# schem.net
KiCad netlist of a schematic drawn in EasyEDA
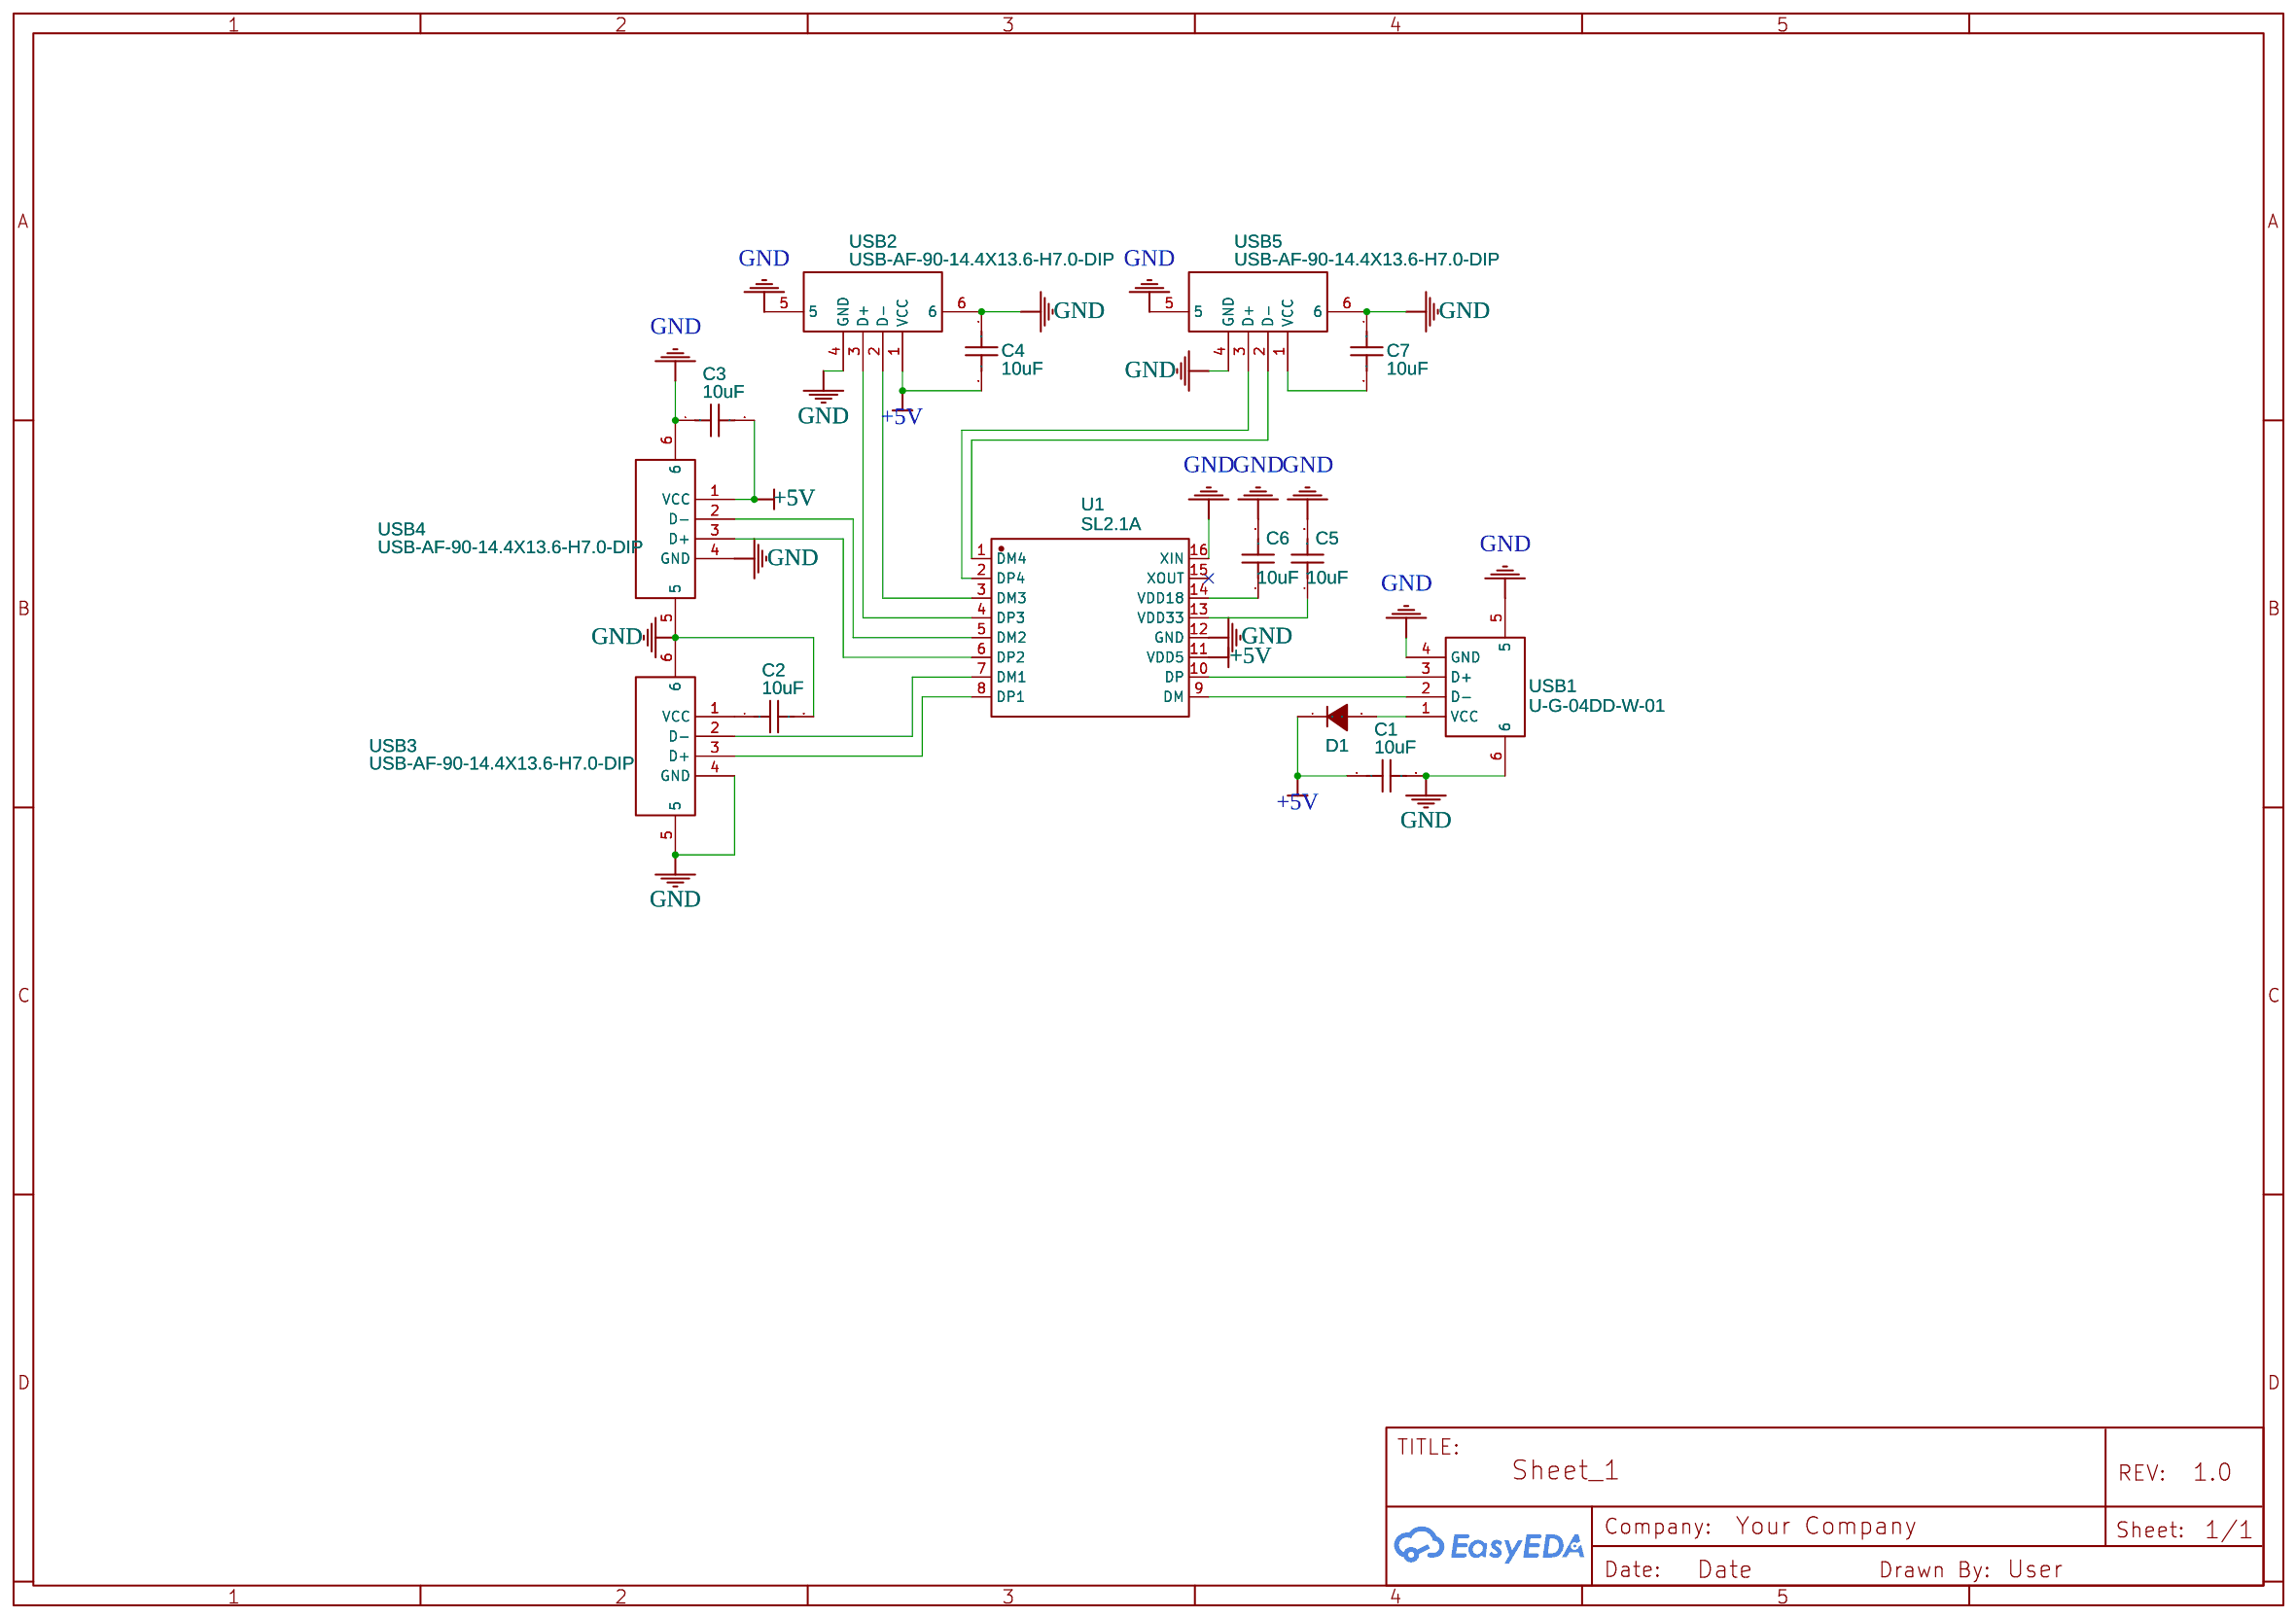
[diagram p0: schematic sheet]

(export (version "E")
  (design (tool "Eeschema 10.0.6"))
  (components
    (comp (ref "C1")
      (value "10uF")
      (fields
        (field (name "Manufacturer Part") "CL10A106KP8NNNC")
        (field (name "Manufacturer") "SAMSUNG(三星)")
      )
      (libsource (lib "") (part "CL10A106KP8NNNC"))
    )
    (comp (ref "C2")
      (value "10uF")
      (fields
        (field (name "Manufacturer Part") "CL10A106KP8NNNC")
        (field (name "Manufacturer") "SAMSUNG(三星)")
      )
      (libsource (lib "") (part "CL10A106KP8NNNC"))
    )
    (comp (ref "C3")
      (value "10uF")
      (fields
        (field (name "Manufacturer Part") "CL10A106KP8NNNC")
        (field (name "Manufacturer") "SAMSUNG(三星)")
      )
      (libsource (lib "") (part "CL10A106KP8NNNC"))
    )
    (comp (ref "C4")
      (value "10uF")
      (fields
        (field (name "Manufacturer Part") "CL10A106KP8NNNC")
        (field (name "Manufacturer") "SAMSUNG(三星)")
      )
      (libsource (lib "") (part "CL10A106KP8NNNC_2"))
    )
    (comp (ref "C5")
      (value "10uF")
      (fields
        (field (name "Manufacturer Part") "CL10A106KP8NNNC")
        (field (name "Manufacturer") "SAMSUNG(三星)")
      )
      (libsource (lib "") (part "CL10A106KP8NNNC_1"))
    )
    (comp (ref "C6")
      (value "10uF")
      (fields
        (field (name "Manufacturer Part") "CL10A106KP8NNNC")
        (field (name "Manufacturer") "SAMSUNG(三星)")
      )
      (libsource (lib "") (part "CL10A106KP8NNNC_1"))
    )
    (comp (ref "C7")
      (value "10uF")
      (fields
        (field (name "Manufacturer Part") "CL10A106KP8NNNC")
        (field (name "Manufacturer") "SAMSUNG(三星)")
      )
      (libsource (lib "") (part "CL10A106KP8NNNC_2"))
    )
    (comp (ref "D1")
      (value "NSR0320MW2T1G")
      (fields (field (name "Manufacturer") "onsemi(安森美)"))
      (libsource (lib "") (part "NSR0320MW2T1G"))
    )
    (comp (ref "U1")
      (value "SL2.1A")
      (fields (field (name "Manufacturer") "CoreChips(和芯润德)"))
      (libsource (lib "") (part "SL2.1A"))
    )
    (comp (ref "USB1")
      (value "U-G-04DD-W-01")
      (fields (field (name "Manufacturer Part") "U-G-O4DD-W-1") (field (name "Manufacturer") "韩国韩荣"))
      (libsource (lib "") (part "U-G-04DD-W-01"))
    )
    (comp (ref "USB2")
      (value "USB-AF-90-14.4X13.6-H7.0-DIP")
      (fields (field (name "Manufacturer Part") "903-131A1011D10100") (field (name "Manufacturer") "精拓金"))
      (libsource (lib "") (part "USB-AF-90-14.4X13.6-H7.0-DIP_1"))
    )
    (comp (ref "USB3")
      (value "USB-AF-90-14.4X13.6-H7.0-DIP")
      (fields (field (name "Manufacturer Part") "903-131A1011D10100") (field (name "Manufacturer") "精拓金"))
      (libsource (lib "") (part "USB-AF-90-14.4X13.6-H7.0-DIP"))
    )
    (comp (ref "USB4")
      (value "USB-AF-90-14.4X13.6-H7.0-DIP")
      (fields (field (name "Manufacturer Part") "903-131A1011D10100") (field (name "Manufacturer") "精拓金"))
      (libsource (lib "") (part "USB-AF-90-14.4X13.6-H7.0-DIP"))
    )
    (comp (ref "USB5")
      (value "USB-AF-90-14.4X13.6-H7.0-DIP")
      (fields (field (name "Manufacturer Part") "903-131A1011D10100") (field (name "Manufacturer") "精拓金"))
      (libsource (lib "") (part "USB-AF-90-14.4X13.6-H7.0-DIP_1"))
    )
  )
  (nets
    (net (code "1") (name "+5V") (class "Default")
      (node (ref "C1") (pin "1") (pinfunction "1_1") (pintype "unspecified"))
      (node (ref "C3") (pin "2") (pinfunction "2_2") (pintype "unspecified"))
      (node (ref "C4") (pin "2") (pinfunction "2_2") (pintype "unspecified"))
      (node (ref "D1") (pin "1") (pinfunction "C_1") (pintype "unspecified"))
      (node (ref "U1") (pin "11") (pinfunction "VDD5_11") (pintype "unspecified"))
      (node (ref "USB2") (pin "1") (pinfunction "VCC_1") (pintype "unspecified"))
      (node (ref "USB4") (pin "1") (pinfunction "VCC_1") (pintype "unspecified"))
    )
    (net (code "2") (name "GND") (class "Default")
      (node (ref "C1") (pin "2") (pinfunction "2_2") (pintype "unspecified"))
      (node (ref "C2") (pin "2") (pinfunction "2_2") (pintype "unspecified"))
      (node (ref "C3") (pin "1") (pinfunction "1_1") (pintype "unspecified"))
      (node (ref "C4") (pin "1") (pinfunction "1_1") (pintype "unspecified"))
      (node (ref "C5") (pin "2") (pinfunction "2_2") (pintype "unspecified"))
      (node (ref "C6") (pin "2") (pinfunction "2_2") (pintype "unspecified"))
      (node (ref "C7") (pin "1") (pinfunction "1_1") (pintype "unspecified"))
      (node (ref "U1") (pin "12") (pinfunction "GND_12") (pintype "unspecified"))
      (node (ref "U1") (pin "16") (pinfunction "XIN_16") (pintype "unspecified"))
      (node (ref "USB1") (pin "4") (pinfunction "GND_4") (pintype "unspecified"))
      (node (ref "USB1") (pin "5") (pinfunction "5_5") (pintype "unspecified"))
      (node (ref "USB1") (pin "6") (pinfunction "6_6") (pintype "unspecified"))
      (node (ref "USB2") (pin "4") (pinfunction "GND_4") (pintype "unspecified"))
      (node (ref "USB2") (pin "5") (pinfunction "5_5") (pintype "unspecified"))
      (node (ref "USB2") (pin "6") (pinfunction "6_6") (pintype "unspecified"))
      (node (ref "USB3") (pin "4") (pinfunction "GND_4") (pintype "unspecified"))
      (node (ref "USB3") (pin "5") (pinfunction "5_5") (pintype "unspecified"))
      (node (ref "USB3") (pin "6") (pinfunction "6_6") (pintype "unspecified"))
      (node (ref "USB4") (pin "4") (pinfunction "GND_4") (pintype "unspecified"))
      (node (ref "USB4") (pin "5") (pinfunction "5_5") (pintype "unspecified"))
      (node (ref "USB4") (pin "6") (pinfunction "6_6") (pintype "unspecified"))
      (node (ref "USB5") (pin "4") (pinfunction "GND_4") (pintype "unspecified"))
      (node (ref "USB5") (pin "5") (pinfunction "5_5") (pintype "unspecified"))
      (node (ref "USB5") (pin "6") (pinfunction "6_6") (pintype "unspecified"))
    )
    (net (code "3") (name "Net-(D1-A)") (class "Default")
      (node (ref "D1") (pin "2") (pinfunction "A_2") (pintype "unspecified"))
      (node (ref "USB1") (pin "1") (pinfunction "VCC_1") (pintype "unspecified"))
    )
    (net (code "4") (name "Net-(U1-DM)") (class "Default")
      (node (ref "U1") (pin "9") (pinfunction "DM_9") (pintype "unspecified"))
      (node (ref "USB1") (pin "2") (pinfunction "D-_2") (pintype "unspecified"))
    )
    (net (code "5") (name "Net-(U1-DM1)") (class "Default")
      (node (ref "U1") (pin "7") (pinfunction "DM1_7") (pintype "unspecified"))
      (node (ref "USB3") (pin "2") (pinfunction "D-_2") (pintype "unspecified"))
    )
    (net (code "6") (name "Net-(U1-DM2)") (class "Default")
      (node (ref "U1") (pin "5") (pinfunction "DM2_5") (pintype "unspecified"))
      (node (ref "USB4") (pin "2") (pinfunction "D-_2") (pintype "unspecified"))
    )
    (net (code "7") (name "Net-(U1-DM3)") (class "Default")
      (node (ref "U1") (pin "3") (pinfunction "DM3_3") (pintype "unspecified"))
      (node (ref "USB2") (pin "2") (pinfunction "D-_2") (pintype "unspecified"))
    )
    (net (code "8") (name "Net-(U1-DM4)") (class "Default")
      (node (ref "U1") (pin "1") (pinfunction "DM4_1") (pintype "unspecified"))
      (node (ref "USB5") (pin "2") (pinfunction "D-_2") (pintype "unspecified"))
    )
    (net (code "9") (name "Net-(U1-DP)") (class "Default")
      (node (ref "U1") (pin "10") (pinfunction "DP_10") (pintype "unspecified"))
      (node (ref "USB1") (pin "3") (pinfunction "D+_3") (pintype "unspecified"))
    )
    (net (code "10") (name "Net-(U1-DP1)") (class "Default")
      (node (ref "U1") (pin "8") (pinfunction "DP1_8") (pintype "unspecified"))
      (node (ref "USB3") (pin "3") (pinfunction "D+_3") (pintype "unspecified"))
    )
    (net (code "11") (name "Net-(U1-DP2)") (class "Default")
      (node (ref "U1") (pin "6") (pinfunction "DP2_6") (pintype "unspecified"))
      (node (ref "USB4") (pin "3") (pinfunction "D+_3") (pintype "unspecified"))
    )
    (net (code "12") (name "Net-(U1-DP3)") (class "Default")
      (node (ref "U1") (pin "4") (pinfunction "DP3_4") (pintype "unspecified"))
      (node (ref "USB2") (pin "3") (pinfunction "D+_3") (pintype "unspecified"))
    )
    (net (code "13") (name "Net-(U1-DP4)") (class "Default")
      (node (ref "U1") (pin "2") (pinfunction "DP4_2") (pintype "unspecified"))
      (node (ref "USB5") (pin "3") (pinfunction "D+_3") (pintype "unspecified"))
    )
    (net (code "14") (name "Net-(U1-VDD18)") (class "Default")
      (node (ref "C6") (pin "1") (pinfunction "1_1") (pintype "unspecified"))
      (node (ref "U1") (pin "14") (pinfunction "VDD18_14") (pintype "unspecified"))
    )
    (net (code "15") (name "Net-(U1-VDD33)") (class "Default")
      (node (ref "C5") (pin "1") (pinfunction "1_1") (pintype "unspecified"))
      (node (ref "U1") (pin "13") (pinfunction "VDD33_13") (pintype "unspecified"))
    )
    (net (code "16") (name "Net-(USB3-VCC)") (class "Default")
      (node (ref "C2") (pin "1") (pinfunction "1_1") (pintype "unspecified"))
      (node (ref "USB3") (pin "1") (pinfunction "VCC_1") (pintype "unspecified"))
    )
    (net (code "17") (name "Net-(USB5-VCC)") (class "Default")
      (node (ref "C7") (pin "2") (pinfunction "2_2") (pintype "unspecified"))
      (node (ref "USB5") (pin "1") (pinfunction "VCC_1") (pintype "unspecified"))
    )
    (net (code "18") (name "unconnected-(U1-XOUT-Pad15)") (class "Default")
      (node (ref "U1") (pin "15") (pinfunction "XOUT_15") (pintype "unspecified+no_connect"))
    )
  )
)
